# master.net
KiCad netlist of a schematic drawn in EAGLE
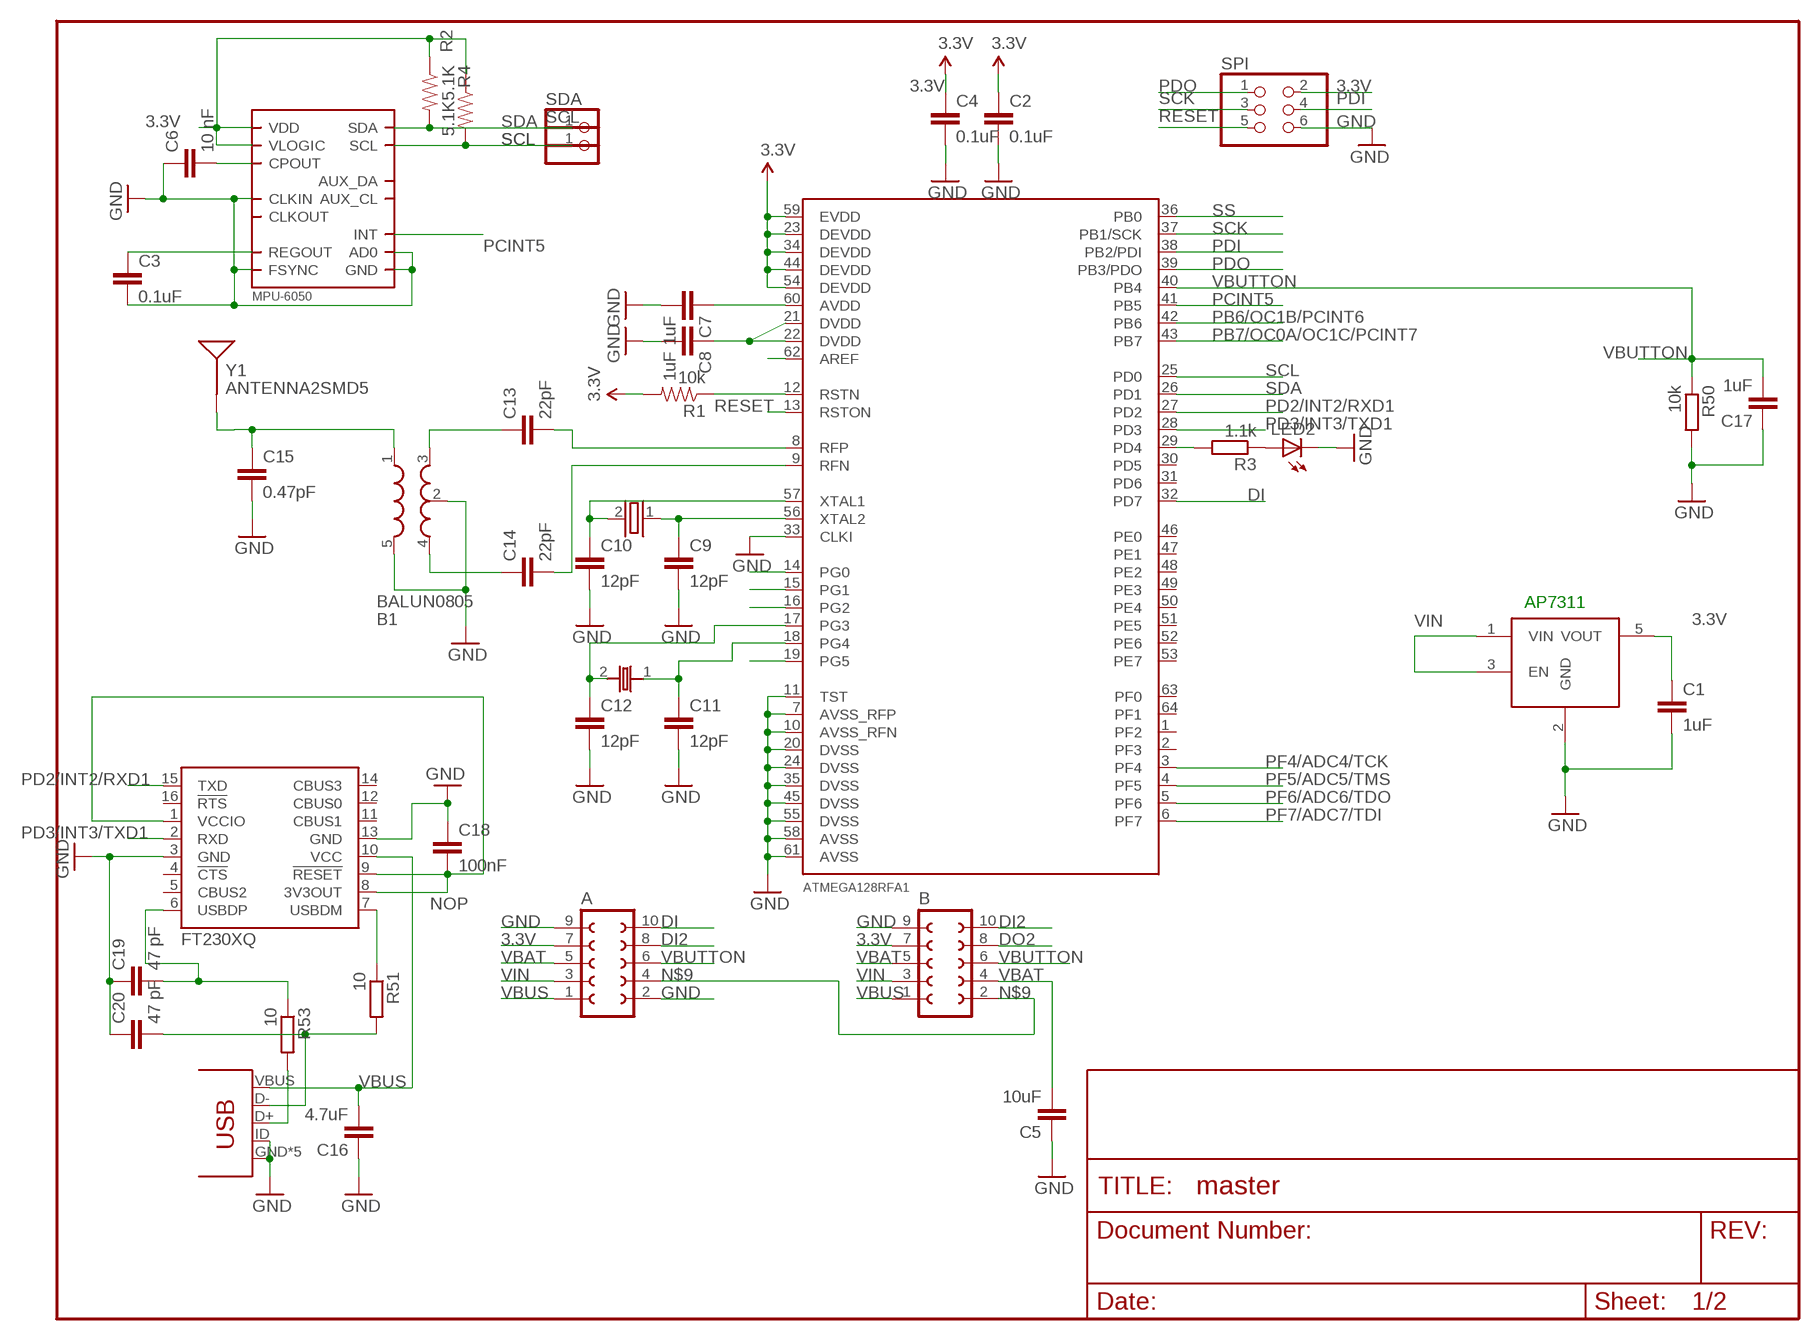
[diagram p0: schematic, sheet 1]

(export (version "E")
  (design (tool "Eeschema 10.0.6"))
  (components
    (comp (ref "A")
      (value "FE05-2W")
      (footprint "eagle-import:FE05-2W")
      (libsource (lib "eagle-import") (part "FE05-2W"))
    )
    (comp (ref "B")
      (value "FE05-2W")
      (footprint "eagle-import:FE05-2W")
      (libsource (lib "eagle-import") (part "FE05-2W"))
    )
    (comp (ref "B1")
      (value "BALUN0805")
      (footprint "eagle-import:BALUN")
      (libsource (lib "eagle-import") (part "BALUN0805"))
    )
    (comp (ref "C1")
      (value "1uF")
      (footprint "eagle-import:C0603")
      (libsource (lib "eagle-import") (part "C-EUC0603"))
    )
    (comp (ref "C2")
      (value "0.1uF")
      (footprint "eagle-import:0603-CAP")
      (libsource (lib "eagle-import") (part "CAP0603-CAP"))
    )
    (comp (ref "C3")
      (value "0.1uF")
      (footprint "eagle-import:0603-CAP")
      (libsource (lib "eagle-import") (part "CAP0603-CAP"))
    )
    (comp (ref "C4")
      (value "0.1uF")
      (footprint "eagle-import:0603-CAP")
      (libsource (lib "eagle-import") (part "CAP0603-CAP"))
    )
    (comp (ref "C5")
      (value "10uF")
      (footprint "eagle-import:0603-CAP")
      (libsource (lib "eagle-import") (part "CAP0603-CAP"))
    )
    (comp (ref "C6")
      (value "10 nF")
      (footprint "eagle-import:0603-CAP")
      (libsource (lib "eagle-import") (part "CAP0603-CAP"))
    )
    (comp (ref "C7")
      (value "1uF")
      (footprint "eagle-import:0805")
      (libsource (lib "eagle-import") (part "CAP0805"))
    )
    (comp (ref "C8")
      (value "1uF")
      (footprint "eagle-import:0805")
      (libsource (lib "eagle-import") (part "CAP0805"))
    )
    (comp (ref "C9")
      (value "12pF")
      (footprint "eagle-import:0603-CAP")
      (libsource (lib "eagle-import") (part "CAP0603-CAP"))
    )
    (comp (ref "C10")
      (value "12pF")
      (footprint "eagle-import:0603-CAP")
      (libsource (lib "eagle-import") (part "CAP0603-CAP"))
    )
    (comp (ref "C11")
      (value "12pF")
      (footprint "eagle-import:0603-CAP")
      (libsource (lib "eagle-import") (part "CAP0603-CAP"))
    )
    (comp (ref "C12")
      (value "12pF")
      (footprint "eagle-import:0603-CAP")
      (libsource (lib "eagle-import") (part "CAP0603-CAP"))
    )
    (comp (ref "C13")
      (value "22pF")
      (footprint "eagle-import:0603-CAP")
      (libsource (lib "eagle-import") (part "CAP0603-CAP"))
    )
    (comp (ref "C14")
      (value "22pF")
      (footprint "eagle-import:0603-CAP")
      (libsource (lib "eagle-import") (part "CAP0603-CAP"))
    )
    (comp (ref "C15")
      (value "0.47pF")
      (footprint "eagle-import:0603-CAP")
      (libsource (lib "eagle-import") (part "CAP0603-CAP"))
    )
    (comp (ref "C16")
      (value "4.7uF")
      (footprint "eagle-import:0603-CAP")
      (libsource (lib "eagle-import") (part "CAP0603-CAP"))
    )
    (comp (ref "C17")
      (value "1uF")
      (footprint "eagle-import:0805")
      (libsource (lib "eagle-import") (part "CAP0805"))
    )
    (comp (ref "C18")
      (value "100nF")
      (footprint "eagle-import:0603-CAP")
      (libsource (lib "eagle-import") (part "CAP0603-CAP"))
    )
    (comp (ref "C19")
      (value "47 pF")
      (footprint "eagle-import:0603-CAP")
      (libsource (lib "eagle-import") (part "CAP0603-CAP"))
    )
    (comp (ref "C20")
      (value "47 pF")
      (footprint "eagle-import:0603-CAP")
      (libsource (lib "eagle-import") (part "CAP0603-CAP"))
    )
    (comp (ref "IC1")
      (value "FT230XQ")
      (footprint "eagle-import:QFN16")
      (libsource (lib "eagle-import") (part "FT230XQ"))
    )
    (comp (ref "LED2")
      (value "LEDCHIPLED_0603")
      (footprint "eagle-import:CHIPLED_0603")
      (libsource (lib "eagle-import") (part "LEDCHIPLED_0603"))
    )
    (comp (ref "MICRO-USB")
      (value "USB-CONNECTOR")
      (footprint "eagle-import:MICRO-USB-435-645")
      (libsource (lib "eagle-import") (part "USB-CONNECTOR"))
    )
    (comp (ref "QUARTZ1")
      (value "753-7203")
      (footprint "eagle-import:753-7203")
      (libsource (lib "eagle-import") (part "753-7203"))
    )
    (comp (ref "QUARTZ2")
      (value "QUARTZ32768")
      (footprint "eagle-import:QUARTZ32768")
      (libsource (lib "eagle-import") (part "QUARTZ32768"))
    )
    (comp (ref "R1")
      (value "10k")
      (footprint "eagle-import:0603-RES")
      (libsource (lib "eagle-import") (part "RESISTOR0603-RES"))
    )
    (comp (ref "R2")
      (value "5.1K")
      (footprint "eagle-import:0603-RES")
      (libsource (lib "eagle-import") (part "RESISTOR0603-RES"))
    )
    (comp (ref "R3")
      (value "1.1k")
      (footprint "eagle-import:R0603")
      (libsource (lib "eagle-import") (part "R-EU_R0603"))
    )
    (comp (ref "R4")
      (value "5.1K")
      (footprint "eagle-import:0603-RES")
      (libsource (lib "eagle-import") (part "RESISTOR0603-RES"))
    )
    (comp (ref "R50")
      (value "10k")
      (footprint "eagle-import:R0603")
      (libsource (lib "eagle-import") (part "R-EU_R0603"))
    )
    (comp (ref "R51")
      (value "10")
      (footprint "eagle-import:R0603")
      (libsource (lib "eagle-import") (part "R-EU_R0603"))
    )
    (comp (ref "R53")
      (value "10")
      (footprint "eagle-import:R0603")
      (libsource (lib "eagle-import") (part "R-EU_R0603"))
    )
    (comp (ref "SCL")
      (value "PINHD-1X1")
      (footprint "eagle-import:1X01")
      (libsource (lib "eagle-import") (part "PINHD-1X1"))
    )
    (comp (ref "SDA")
      (value "PINHD-1X1")
      (footprint "eagle-import:1X01")
      (libsource (lib "eagle-import") (part "PINHD-1X1"))
    )
    (comp (ref "SPI")
      (value "PINHD-2X3")
      (footprint "eagle-import:2X03")
      (libsource (lib "eagle-import") (part "PINHD-2X3"))
    )
    (comp (ref "U$1")
      (value "MPU-6050")
      (footprint "eagle-import:QFN.24.4X4")
      (libsource (lib "eagle-import") (part "MPU-6050"))
    )
    (comp (ref "U$7")
      (value "MIC5366-2.8YMT")
      (footprint "eagle-import:SOT23-5")
      (libsource (lib "eagle-import") (part "MIC5366-2.8YMT"))
    )
    (comp (ref "U1")
      (value "ATMEGA128RFA1")
      (footprint "eagle-import:QFN-64")
      (libsource (lib "eagle-import") (part "ATMEGA128RFA1"))
    )
    (comp (ref "Y1")
      (value "ANTENNA2SMD5")
      (footprint "eagle-import:ANTENNA-CHIP5")
      (libsource (lib "eagle-import") (part "ANTENNA2SMD5"))
    )
  )
  (nets
    (net (code "1") (name "3.3V") (class "Default")
      (node (ref "A") (pin "7") (pinfunction "7_7") (pintype "passive"))
      (node (ref "B") (pin "7") (pinfunction "7_7") (pintype "passive"))
      (node (ref "C1") (pin "1") (pinfunction "1_1") (pintype "passive"))
      (node (ref "C2") (pin "1") (pinfunction "1_1") (pintype "passive"))
      (node (ref "C4") (pin "1") (pinfunction "1_1") (pintype "passive"))
      (node (ref "R1") (pin "2") (pinfunction "2_2") (pintype "passive"))
      (node (ref "R2") (pin "1") (pinfunction "1_1") (pintype "passive"))
      (node (ref "R4") (pin "1") (pinfunction "1_1") (pintype "passive"))
      (node (ref "SPI") (pin "2") (pinfunction "2_2") (pintype "passive"))
      (node (ref "U$1") (pin "13") (pinfunction "VDD_13") (pintype "bidirectional"))
      (node (ref "U$1") (pin "8") (pinfunction "VLOGIC_8") (pintype "bidirectional"))
      (node (ref "U$7") (pin "5") (pinfunction "VOUT_5") (pintype "bidirectional"))
      (node (ref "U1") (pin "23") (pinfunction "DEVDD_23") (pintype "bidirectional"))
      (node (ref "U1") (pin "34") (pinfunction "DEVDD_34") (pintype "bidirectional"))
      (node (ref "U1") (pin "44") (pinfunction "DEVDD_44") (pintype "bidirectional"))
      (node (ref "U1") (pin "54") (pinfunction "DEVDD_54") (pintype "bidirectional"))
      (node (ref "U1") (pin "59") (pinfunction "EVDD_59") (pintype "bidirectional"))
    )
    (net (code "2") (name "DI") (class "Default")
      (node (ref "A") (pin "10") (pinfunction "10_10") (pintype "passive"))
      (node (ref "U1") (pin "32") (pinfunction "PD7_32") (pintype "bidirectional"))
    )
    (net (code "3") (name "DI2") (class "Default")
      (node (ref "A") (pin "8") (pinfunction "8_8") (pintype "passive"))
      (node (ref "B") (pin "10") (pinfunction "10_10") (pintype "passive"))
    )
    (net (code "4") (name "DO2") (class "Default")
      (node (ref "B") (pin "8") (pinfunction "8_8") (pintype "passive"))
    )
    (net (code "5") (name "GND") (class "Default")
      (node (ref "A") (pin "2") (pinfunction "2_2") (pintype "passive"))
      (node (ref "A") (pin "9") (pinfunction "9_9") (pintype "passive"))
      (node (ref "B") (pin "9") (pinfunction "9_9") (pintype "passive"))
      (node (ref "B1") (pin "2") (pinfunction "GND_2") (pintype "bidirectional"))
      (node (ref "B1") (pin "5") (pinfunction "GND_5") (pintype "bidirectional"))
      (node (ref "C1") (pin "2") (pinfunction "2_2") (pintype "passive"))
      (node (ref "C10") (pin "2") (pinfunction "2_2") (pintype "passive"))
      (node (ref "C11") (pin "2") (pinfunction "2_2") (pintype "passive"))
      (node (ref "C12") (pin "2") (pinfunction "2_2") (pintype "passive"))
      (node (ref "C15") (pin "2") (pinfunction "2_2") (pintype "passive"))
      (node (ref "C16") (pin "1") (pinfunction "1_1") (pintype "passive"))
      (node (ref "C17") (pin "1") (pinfunction "1_1") (pintype "passive"))
      (node (ref "C18") (pin "1") (pinfunction "1_1") (pintype "passive"))
      (node (ref "C19") (pin "1") (pinfunction "1_1") (pintype "passive"))
      (node (ref "C2") (pin "2") (pinfunction "2_2") (pintype "passive"))
      (node (ref "C20") (pin "1") (pinfunction "1_1") (pintype "passive"))
      (node (ref "C3") (pin "2") (pinfunction "2_2") (pintype "passive"))
      (node (ref "C4") (pin "2") (pinfunction "2_2") (pintype "passive"))
      (node (ref "C5") (pin "1") (pinfunction "1_1") (pintype "passive"))
      (node (ref "C6") (pin "1") (pinfunction "1_1") (pintype "passive"))
      (node (ref "C7") (pin "2") (pinfunction "2_2") (pintype "passive"))
      (node (ref "C8") (pin "2") (pinfunction "2_2") (pintype "passive"))
      (node (ref "C9") (pin "2") (pinfunction "2_2") (pintype "passive"))
      (node (ref "IC1") (pin "13") (pinfunction "GND_13") (pintype "power_in"))
      (node (ref "IC1") (pin "3") (pinfunction "GND_3") (pintype "power_in"))
      (node (ref "LED2") (pin "C") (pinfunction "C_C") (pintype "passive"))
      (node (ref "MICRO-USB") (pin "GND") (pinfunction "GND_GND") (pintype "bidirectional"))
      (node (ref "MICRO-USB") (pin "GND1") (pinfunction "GND_GND1") (pintype "bidirectional"))
      (node (ref "MICRO-USB") (pin "GND2") (pinfunction "GND_GND2") (pintype "bidirectional"))
      (node (ref "MICRO-USB") (pin "GND3") (pinfunction "GND_GND3") (pintype "bidirectional"))
      (node (ref "MICRO-USB") (pin "GND4") (pinfunction "GND_GND4") (pintype "bidirectional"))
      (node (ref "MICRO-USB") (pin "ID") (pinfunction "ID_ID") (pintype "bidirectional"))
      (node (ref "R50") (pin "2") (pinfunction "2_2") (pintype "passive"))
      (node (ref "SPI") (pin "6") (pinfunction "6_6") (pintype "passive"))
      (node (ref "U$1") (pin "1") (pinfunction "CLKIN_1") (pintype "bidirectional"))
      (node (ref "U$1") (pin "11") (pinfunction "FSYNC_11") (pintype "bidirectional"))
      (node (ref "U$1") (pin "18") (pinfunction "GND_18") (pintype "bidirectional"))
      (node (ref "U$1") (pin "9") (pinfunction "AD0_9") (pintype "bidirectional"))
      (node (ref "U$7") (pin "2") (pinfunction "GND_2") (pintype "bidirectional"))
      (node (ref "U1") (pin "10") (pinfunction "AVSS_RFN_10") (pintype "bidirectional"))
      (node (ref "U1") (pin "11") (pinfunction "TST_11") (pintype "bidirectional"))
      (node (ref "U1") (pin "20") (pinfunction "DVSS_20") (pintype "bidirectional"))
      (node (ref "U1") (pin "24") (pinfunction "DVSS_24") (pintype "bidirectional"))
      (node (ref "U1") (pin "33") (pinfunction "CLKI_33") (pintype "bidirectional"))
      (node (ref "U1") (pin "35") (pinfunction "DVSS_35") (pintype "bidirectional"))
      (node (ref "U1") (pin "45") (pinfunction "DVSS_45") (pintype "bidirectional"))
      (node (ref "U1") (pin "55") (pinfunction "DVSS_55") (pintype "bidirectional"))
      (node (ref "U1") (pin "58") (pinfunction "AVSS_58") (pintype "bidirectional"))
      (node (ref "U1") (pin "61") (pinfunction "AVSS_61") (pintype "bidirectional"))
      (node (ref "U1") (pin "7") (pinfunction "AVSS_RFP_7") (pintype "bidirectional"))
    )
    (net (code "6") (name "N$9") (class "Default")
      (node (ref "A") (pin "4") (pinfunction "4_4") (pintype "passive"))
      (node (ref "B") (pin "2") (pinfunction "2_2") (pintype "passive"))
    )
    (net (code "7") (name "NOP") (class "Default")
      (node (ref "C18") (pin "2") (pinfunction "2_2") (pintype "passive"))
      (node (ref "IC1") (pin "1") (pinfunction "VCCIO_1") (pintype "power_in"))
      (node (ref "IC1") (pin "8") (pinfunction "3V3OUT_8") (pintype "output"))
      (node (ref "IC1") (pin "9") (pinfunction "~{RESET}_9") (pintype "input"))
    )
    (net (code "8") (name "Net-(B1-IN)") (class "Default")
      (node (ref "B1") (pin "1") (pinfunction "IN_1") (pintype "bidirectional"))
      (node (ref "C15") (pin "1") (pinfunction "1_1") (pintype "passive"))
      (node (ref "Y1") (pin "FEED") (pinfunction "SIGNAL_FEED") (pintype "bidirectional"))
    )
    (net (code "9") (name "Net-(B1-OUT1)") (class "Default")
      (node (ref "B1") (pin "3") (pinfunction "OUT1_3") (pintype "bidirectional"))
      (node (ref "C13") (pin "1") (pinfunction "1_1") (pintype "passive"))
    )
    (net (code "10") (name "Net-(B1-OUT2)") (class "Default")
      (node (ref "B1") (pin "4") (pinfunction "OUT2_4") (pintype "bidirectional"))
      (node (ref "C14") (pin "1") (pinfunction "1_1") (pintype "passive"))
    )
    (net (code "11") (name "Net-(C8-Pad1)") (class "Default")
      (node (ref "C8") (pin "1") (pinfunction "1_1") (pintype "passive"))
      (node (ref "U1") (pin "21") (pinfunction "DVDD_21") (pintype "bidirectional"))
      (node (ref "U1") (pin "22") (pinfunction "DVDD_22") (pintype "bidirectional"))
    )
    (net (code "12") (name "Net-(C20-Pad2)") (class "Default")
      (node (ref "C20") (pin "2") (pinfunction "2_2") (pintype "passive"))
      (node (ref "MICRO-USB") (pin "D-") (pinfunction "D-_D-") (pintype "bidirectional"))
      (node (ref "R51") (pin "2") (pinfunction "2_2") (pintype "passive"))
    )
    (net (code "13") (name "Net-(IC1-USBDM)") (class "Default")
      (node (ref "IC1") (pin "7") (pinfunction "USBDM_7") (pintype "input"))
      (node (ref "R51") (pin "1") (pinfunction "1_1") (pintype "passive"))
    )
    (net (code "14") (name "Net-(IC1-USBDP)") (class "Default")
      (node (ref "C19") (pin "2") (pinfunction "2_2") (pintype "passive"))
      (node (ref "IC1") (pin "6") (pinfunction "USBDP_6") (pintype "input"))
      (node (ref "R53") (pin "1") (pinfunction "1_1") (pintype "passive"))
    )
    (net (code "15") (name "Net-(LED2-PadA)") (class "Default")
      (node (ref "LED2") (pin "A") (pinfunction "A_A") (pintype "passive"))
      (node (ref "R3") (pin "1") (pinfunction "1_1") (pintype "passive"))
    )
    (net (code "16") (name "Net-(MICRO-USB-PadD+)") (class "Default")
      (node (ref "MICRO-USB") (pin "D+") (pinfunction "D+_D+") (pintype "bidirectional"))
      (node (ref "R53") (pin "2") (pinfunction "2_2") (pintype "passive"))
    )
    (net (code "17") (name "Net-(U$1-CPOUT)") (class "Default")
      (node (ref "C6") (pin "2") (pinfunction "2_2") (pintype "passive"))
      (node (ref "U$1") (pin "20") (pinfunction "CPOUT_20") (pintype "bidirectional"))
    )
    (net (code "18") (name "Net-(U$1-REGOUT)") (class "Default")
      (node (ref "C3") (pin "1") (pinfunction "1_1") (pintype "passive"))
      (node (ref "U$1") (pin "10") (pinfunction "REGOUT_10") (pintype "bidirectional"))
    )
    (net (code "19") (name "Net-(U1-AVDD)") (class "Default")
      (node (ref "C7") (pin "1") (pinfunction "1_1") (pintype "passive"))
      (node (ref "U1") (pin "60") (pinfunction "AVDD_60") (pintype "bidirectional"))
    )
    (net (code "20") (name "Net-(U1-PD4)") (class "Default")
      (node (ref "R3") (pin "2") (pinfunction "2_2") (pintype "passive"))
      (node (ref "U1") (pin "29") (pinfunction "PD4_29") (pintype "bidirectional"))
    )
    (net (code "21") (name "Net-(U1-PG3)") (class "Default")
      (node (ref "C12") (pin "1") (pinfunction "1_1") (pintype "passive"))
      (node (ref "QUARTZ2") (pin "2") (pinfunction "2_2") (pintype "bidirectional"))
      (node (ref "U1") (pin "17") (pinfunction "PG3_17") (pintype "bidirectional"))
    )
    (net (code "22") (name "Net-(U1-PG4)") (class "Default")
      (node (ref "C11") (pin "1") (pinfunction "1_1") (pintype "passive"))
      (node (ref "QUARTZ2") (pin "1") (pinfunction "1_1") (pintype "bidirectional"))
      (node (ref "U1") (pin "18") (pinfunction "PG4_18") (pintype "bidirectional"))
    )
    (net (code "23") (name "Net-(U1-RFN)") (class "Default")
      (node (ref "C14") (pin "2") (pinfunction "2_2") (pintype "passive"))
      (node (ref "U1") (pin "9") (pinfunction "RFN_9") (pintype "bidirectional"))
    )
    (net (code "24") (name "Net-(U1-RFP)") (class "Default")
      (node (ref "C13") (pin "2") (pinfunction "2_2") (pintype "passive"))
      (node (ref "U1") (pin "8") (pinfunction "RFP_8") (pintype "bidirectional"))
    )
    (net (code "25") (name "Net-(U1-XTAL1)") (class "Default")
      (node (ref "C10") (pin "1") (pinfunction "1_1") (pintype "passive"))
      (node (ref "QUARTZ1") (pin "2") (pinfunction "2_2") (pintype "bidirectional"))
      (node (ref "U1") (pin "57") (pinfunction "XTAL1_57") (pintype "bidirectional"))
    )
    (net (code "26") (name "Net-(U1-XTAL2)") (class "Default")
      (node (ref "C9") (pin "1") (pinfunction "1_1") (pintype "passive"))
      (node (ref "QUARTZ1") (pin "1") (pinfunction "1_1") (pintype "bidirectional"))
      (node (ref "U1") (pin "56") (pinfunction "XTAL2_56") (pintype "bidirectional"))
    )
    (net (code "27") (name "PB6{slash}OC1B{slash}PCINT6") (class "Default")
      (node (ref "U1") (pin "42") (pinfunction "PB6_42") (pintype "bidirectional"))
    )
    (net (code "28") (name "PB7{slash}OC0A{slash}OC1C{slash}PCINT7") (class "Default")
      (node (ref "U1") (pin "43") (pinfunction "PB7_43") (pintype "bidirectional"))
    )
    (net (code "29") (name "PCINT5") (class "Default")
      (node (ref "U$1") (pin "12") (pinfunction "INT_12") (pintype "bidirectional"))
      (node (ref "U1") (pin "41") (pinfunction "PB5_41") (pintype "bidirectional"))
    )
    (net (code "30") (name "PD2{slash}INT2{slash}RXD1") (class "Default")
      (node (ref "IC1") (pin "15") (pinfunction "TXD_15") (pintype "output"))
      (node (ref "U1") (pin "27") (pinfunction "PD2_27") (pintype "bidirectional"))
    )
    (net (code "31") (name "PD3{slash}INT3{slash}TXD1") (class "Default")
      (node (ref "IC1") (pin "2") (pinfunction "RXD_2") (pintype "input"))
      (node (ref "U1") (pin "28") (pinfunction "PD3_28") (pintype "bidirectional"))
    )
    (net (code "32") (name "PDI") (class "Default")
      (node (ref "SPI") (pin "4") (pinfunction "4_4") (pintype "passive"))
      (node (ref "U1") (pin "38") (pinfunction "PB2/PDI_38") (pintype "bidirectional"))
    )
    (net (code "33") (name "PDO") (class "Default")
      (node (ref "SPI") (pin "1") (pinfunction "1_1") (pintype "passive"))
      (node (ref "U1") (pin "39") (pinfunction "PB3/PDO_39") (pintype "bidirectional"))
    )
    (net (code "34") (name "PF4{slash}ADC4{slash}TCK") (class "Default")
      (node (ref "U1") (pin "3") (pinfunction "PF4_3") (pintype "bidirectional"))
    )
    (net (code "35") (name "PF5{slash}ADC5{slash}TMS") (class "Default")
      (node (ref "U1") (pin "4") (pinfunction "PF5_4") (pintype "bidirectional"))
    )
    (net (code "36") (name "PF6{slash}ADC6{slash}TDO") (class "Default")
      (node (ref "U1") (pin "5") (pinfunction "PF6_5") (pintype "bidirectional"))
    )
    (net (code "37") (name "PF7{slash}ADC7{slash}TDI") (class "Default")
      (node (ref "U1") (pin "6") (pinfunction "PF7_6") (pintype "bidirectional"))
    )
    (net (code "38") (name "RESET") (class "Default")
      (node (ref "R1") (pin "1") (pinfunction "1_1") (pintype "passive"))
      (node (ref "SPI") (pin "5") (pinfunction "5_5") (pintype "passive"))
      (node (ref "U1") (pin "12") (pinfunction "RSTN_12") (pintype "bidirectional"))
    )
    (net (code "39") (name "SCK") (class "Default")
      (node (ref "SPI") (pin "3") (pinfunction "3_3") (pintype "passive"))
      (node (ref "U1") (pin "37") (pinfunction "PB1/SCK_37") (pintype "bidirectional"))
    )
    (net (code "40") (name "SCL") (class "Default")
      (node (ref "R4") (pin "2") (pinfunction "2_2") (pintype "passive"))
      (node (ref "SCL") (pin "1") (pinfunction "1_1") (pintype "passive"))
      (node (ref "U$1") (pin "23") (pinfunction "SCL_23") (pintype "bidirectional"))
      (node (ref "U1") (pin "25") (pinfunction "PD0_25") (pintype "bidirectional"))
    )
    (net (code "41") (name "SDA") (class "Default")
      (node (ref "R2") (pin "2") (pinfunction "2_2") (pintype "passive"))
      (node (ref "SDA") (pin "1") (pinfunction "1_1") (pintype "passive"))
      (node (ref "U$1") (pin "24") (pinfunction "SDA_24") (pintype "bidirectional"))
      (node (ref "U1") (pin "26") (pinfunction "PD1_26") (pintype "bidirectional"))
    )
    (net (code "42") (name "SS") (class "Default")
      (node (ref "U1") (pin "36") (pinfunction "PB0_36") (pintype "bidirectional"))
    )
    (net (code "43") (name "VBAT") (class "Default")
      (node (ref "A") (pin "5") (pinfunction "5_5") (pintype "passive"))
      (node (ref "B") (pin "4") (pinfunction "4_4") (pintype "passive"))
      (node (ref "B") (pin "5") (pinfunction "5_5") (pintype "passive"))
      (node (ref "C5") (pin "2") (pinfunction "2_2") (pintype "passive"))
    )
    (net (code "44") (name "VBUS") (class "Default")
      (node (ref "A") (pin "1") (pinfunction "1_1") (pintype "passive"))
      (node (ref "B") (pin "1") (pinfunction "1_1") (pintype "passive"))
      (node (ref "C16") (pin "2") (pinfunction "2_2") (pintype "passive"))
      (node (ref "IC1") (pin "10") (pinfunction "VCC_10") (pintype "power_in"))
      (node (ref "MICRO-USB") (pin "VBUS") (pinfunction "VBUS_VBUS") (pintype "bidirectional"))
    )
    (net (code "45") (name "VBUTTON") (class "Default")
      (node (ref "A") (pin "6") (pinfunction "6_6") (pintype "passive"))
      (node (ref "B") (pin "6") (pinfunction "6_6") (pintype "passive"))
      (node (ref "C17") (pin "2") (pinfunction "2_2") (pintype "passive"))
      (node (ref "R50") (pin "1") (pinfunction "1_1") (pintype "passive"))
      (node (ref "U1") (pin "40") (pinfunction "PB4_40") (pintype "bidirectional"))
    )
    (net (code "46") (name "VIN") (class "Default")
      (node (ref "A") (pin "3") (pinfunction "3_3") (pintype "passive"))
      (node (ref "B") (pin "3") (pinfunction "3_3") (pintype "passive"))
      (node (ref "U$7") (pin "1") (pinfunction "VIN_1") (pintype "bidirectional"))
      (node (ref "U$7") (pin "3") (pinfunction "EN_3") (pintype "bidirectional"))
    )
    (net (code "47") (name "unconnected-(IC1-CBUS0-Pad12)") (class "Default")
      (node (ref "IC1") (pin "12") (pinfunction "CBUS0_12") (pintype "bidirectional"))
    )
    (net (code "48") (name "unconnected-(IC1-CBUS1-Pad11)") (class "Default")
      (node (ref "IC1") (pin "11") (pinfunction "CBUS1_11") (pintype "bidirectional"))
    )
    (net (code "49") (name "unconnected-(IC1-CBUS2-Pad5)") (class "Default")
      (node (ref "IC1") (pin "5") (pinfunction "CBUS2_5") (pintype "bidirectional"))
    )
    (net (code "50") (name "unconnected-(IC1-CBUS3-Pad14)") (class "Default")
      (node (ref "IC1") (pin "14") (pinfunction "CBUS3_14") (pintype "bidirectional"))
    )
    (net (code "51") (name "unconnected-(IC1-~{CTS}-Pad4)") (class "Default")
      (node (ref "IC1") (pin "4") (pinfunction "~{CTS}_4") (pintype "input"))
    )
    (net (code "52") (name "unconnected-(IC1-~{RTS}-Pad16)") (class "Default")
      (node (ref "IC1") (pin "16") (pinfunction "~{RTS}_16") (pintype "output"))
    )
    (net (code "53") (name "unconnected-(U$1-AUX_CL-Pad7)") (class "Default")
      (node (ref "U$1") (pin "7") (pinfunction "AUX_CL_7") (pintype "bidirectional"))
    )
    (net (code "54") (name "unconnected-(U$1-AUX_DA-Pad6)") (class "Default")
      (node (ref "U$1") (pin "6") (pinfunction "AUX_DA_6") (pintype "bidirectional"))
    )
    (net (code "55") (name "unconnected-(U$1-CLKOUT-Pad22)") (class "Default")
      (node (ref "U$1") (pin "22") (pinfunction "CLKOUT_22") (pintype "bidirectional"))
    )
    (net (code "56") (name "unconnected-(U1-AREF-Pad62)") (class "Default")
      (node (ref "U1") (pin "62") (pinfunction "AREF_62") (pintype "bidirectional"))
    )
    (net (code "57") (name "unconnected-(U1-PD5-Pad30)") (class "Default")
      (node (ref "U1") (pin "30") (pinfunction "PD5_30") (pintype "bidirectional"))
    )
    (net (code "58") (name "unconnected-(U1-PD6-Pad31)") (class "Default")
      (node (ref "U1") (pin "31") (pinfunction "PD6_31") (pintype "bidirectional"))
    )
    (net (code "59") (name "unconnected-(U1-PE0-Pad46)") (class "Default")
      (node (ref "U1") (pin "46") (pinfunction "PE0_46") (pintype "bidirectional"))
    )
    (net (code "60") (name "unconnected-(U1-PE1-Pad47)") (class "Default")
      (node (ref "U1") (pin "47") (pinfunction "PE1_47") (pintype "bidirectional"))
    )
    (net (code "61") (name "unconnected-(U1-PE2-Pad48)") (class "Default")
      (node (ref "U1") (pin "48") (pinfunction "PE2_48") (pintype "bidirectional"))
    )
    (net (code "62") (name "unconnected-(U1-PE3-Pad49)") (class "Default")
      (node (ref "U1") (pin "49") (pinfunction "PE3_49") (pintype "bidirectional"))
    )
    (net (code "63") (name "unconnected-(U1-PE4-Pad50)") (class "Default")
      (node (ref "U1") (pin "50") (pinfunction "PE4_50") (pintype "bidirectional"))
    )
    (net (code "64") (name "unconnected-(U1-PE5-Pad51)") (class "Default")
      (node (ref "U1") (pin "51") (pinfunction "PE5_51") (pintype "bidirectional"))
    )
    (net (code "65") (name "unconnected-(U1-PE6-Pad52)") (class "Default")
      (node (ref "U1") (pin "52") (pinfunction "PE6_52") (pintype "bidirectional"))
    )
    (net (code "66") (name "unconnected-(U1-PE7-Pad53)") (class "Default")
      (node (ref "U1") (pin "53") (pinfunction "PE7_53") (pintype "bidirectional"))
    )
    (net (code "67") (name "unconnected-(U1-PF0-Pad63)") (class "Default")
      (node (ref "U1") (pin "63") (pinfunction "PF0_63") (pintype "bidirectional"))
    )
    (net (code "68") (name "unconnected-(U1-PF1-Pad64)") (class "Default")
      (node (ref "U1") (pin "64") (pinfunction "PF1_64") (pintype "bidirectional"))
    )
    (net (code "69") (name "unconnected-(U1-PF2-Pad1)") (class "Default")
      (node (ref "U1") (pin "1") (pinfunction "PF2_1") (pintype "bidirectional"))
    )
    (net (code "70") (name "unconnected-(U1-PF3-Pad2)") (class "Default")
      (node (ref "U1") (pin "2") (pinfunction "PF3_2") (pintype "bidirectional"))
    )
    (net (code "71") (name "unconnected-(U1-PG0-Pad14)") (class "Default")
      (node (ref "U1") (pin "14") (pinfunction "PG0_14") (pintype "bidirectional"))
    )
    (net (code "72") (name "unconnected-(U1-PG1-Pad15)") (class "Default")
      (node (ref "U1") (pin "15") (pinfunction "PG1_15") (pintype "bidirectional"))
    )
    (net (code "73") (name "unconnected-(U1-PG2-Pad16)") (class "Default")
      (node (ref "U1") (pin "16") (pinfunction "PG2_16") (pintype "bidirectional"))
    )
    (net (code "74") (name "unconnected-(U1-PG5-Pad19)") (class "Default")
      (node (ref "U1") (pin "19") (pinfunction "PG5_19") (pintype "bidirectional"))
    )
    (net (code "75") (name "unconnected-(U1-RSTON-Pad13)") (class "Default")
      (node (ref "U1") (pin "13") (pinfunction "RSTON_13") (pintype "bidirectional"))
    )
  )
)
